# SCH_floatproj_2024-04-08.net
KiCad netlist of a schematic drawn in EasyEDA
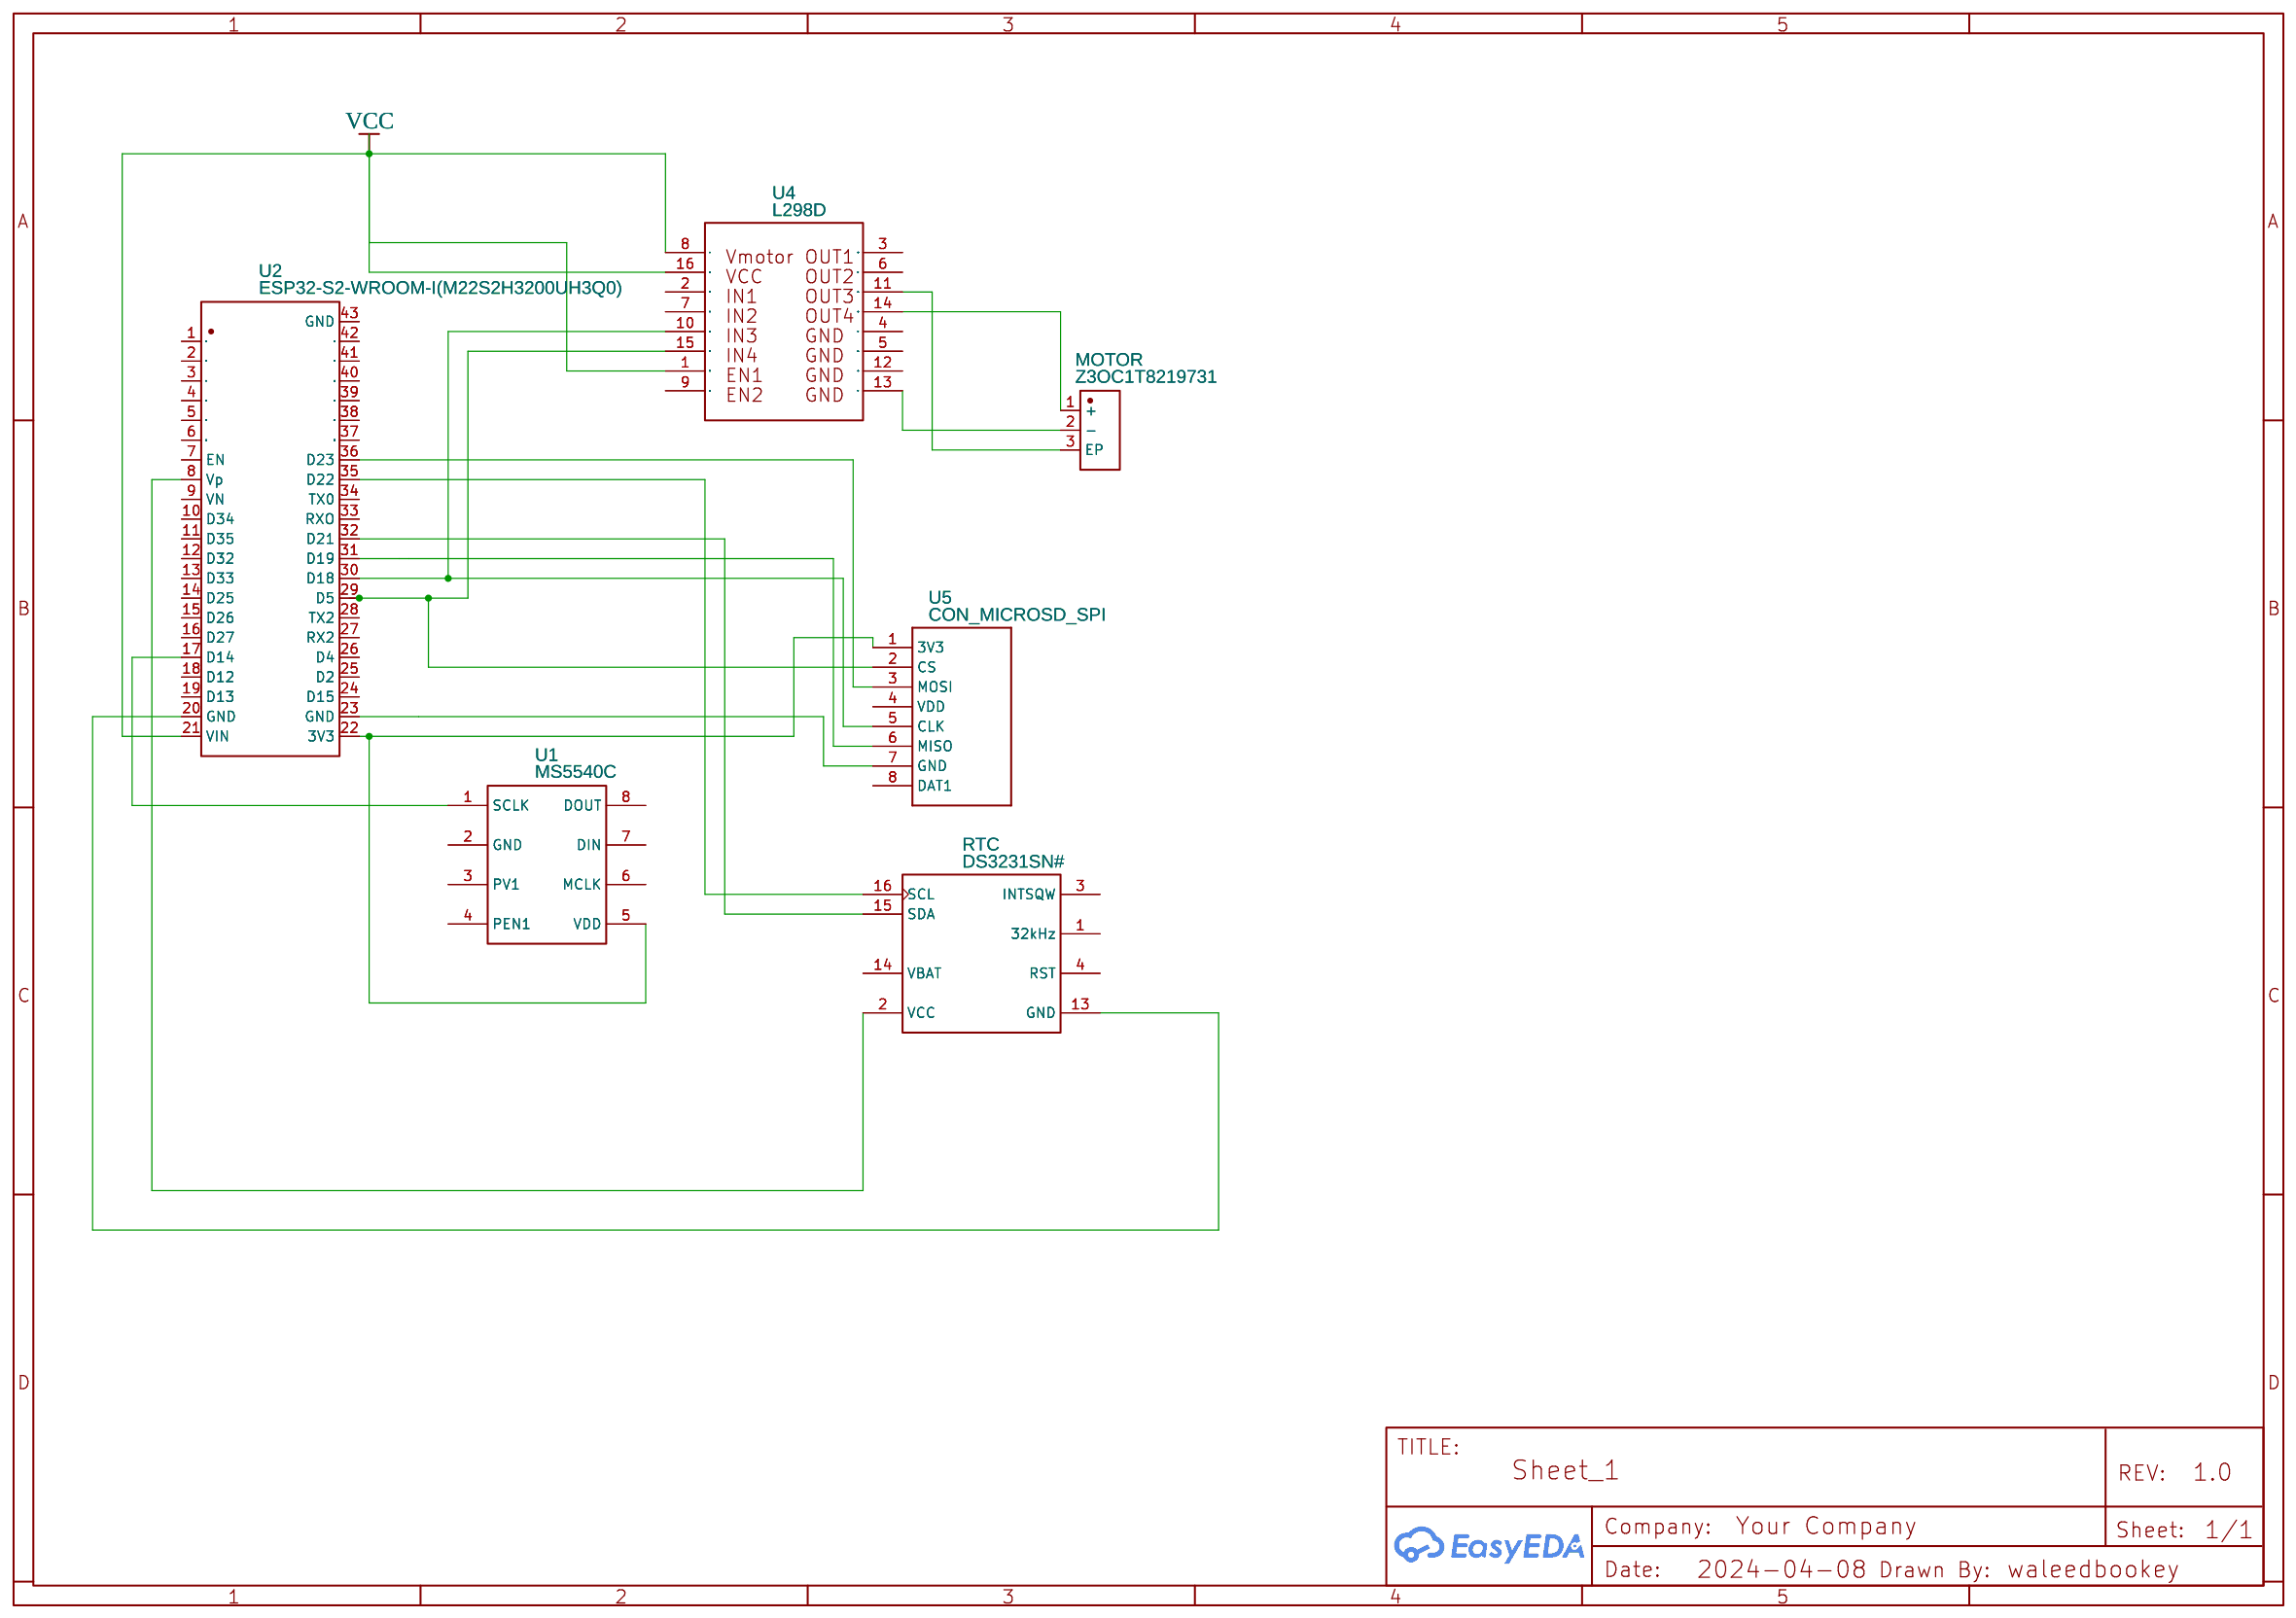
[diagram p0: schematic sheet]

(export (version "E")
  (design (tool "Eeschema 10.0.6"))
  (components
    (comp (ref "MOTOR")
      (value "Z3OC1T8219731")
      (fields (field (name "Manufacturer") "KOTL(金龙机电)"))
      (libsource (lib "") (part "Z3OC1T8219731"))
    )
    (comp (ref "RTC")
      (value "DS3231SN#")
      (fields
        (field (name "Manufacturer Part") "DS3231SN#T&R")
        (field (name "Manufacturer") "ADI(亚德诺)/MAXIM(美信)")
      )
      (libsource (lib "") (part "DS3231SN#"))
    )
    (comp (ref "U1") (value "MS5540C") (libsource (lib "") (part "MS5540C")))
    (comp (ref "U2")
      (value "ESP32-S2-WROOM-I(M22S2H3200UH3Q0)")
      (fields (field (name "Manufacturer") "ESPRESSIF(乐鑫)"))
      (libsource (lib "") (part "ESP32-S2-WROOM-I(M22S2H3200UH3Q0)"))
    )
    (comp (ref "U4") (value "L298D") (libsource (lib "") (part "L298D")))
    (comp (ref "U5") (value "CON_MICROSD_SPI") (libsource (lib "") (part "CON_MICROSD")))
  )
  (nets
    (net (code "1") (name "Net-(MOTOR-+)") (class "Default")
      (node (ref "MOTOR") (pin "1") (pinfunction "+_1") (pintype "unspecified"))
      (node (ref "U4") (pin "14") (pinfunction "15_14") (pintype "unspecified"))
    )
    (net (code "2") (name "Net-(MOTOR--)") (class "Default")
      (node (ref "MOTOR") (pin "2") (pinfunction "-_2") (pintype "unspecified"))
      (node (ref "U4") (pin "13") (pinfunction "11_13") (pintype "unspecified"))
    )
    (net (code "3") (name "Net-(MOTOR-EP)") (class "Default")
      (node (ref "MOTOR") (pin "3") (pinfunction "EP_3") (pintype "unspecified"))
      (node (ref "U4") (pin "11") (pinfunction "16_11") (pintype "unspecified"))
    )
    (net (code "4") (name "Net-(RTC-GND)") (class "Default")
      (node (ref "RTC") (pin "13") (pinfunction "GND_13") (pintype "passive"))
      (node (ref "U2") (pin "20") (pinfunction "GND_20") (pintype "unspecified"))
    )
    (net (code "5") (name "Net-(RTC-SCL)") (class "Default")
      (node (ref "RTC") (pin "16") (pinfunction "SCL_16") (pintype "unspecified"))
      (node (ref "U2") (pin "35") (pinfunction "D22_35") (pintype "unspecified"))
    )
    (net (code "6") (name "Net-(RTC-SDA)") (class "Default")
      (node (ref "RTC") (pin "15") (pinfunction "SDA_15") (pintype "bidirectional"))
      (node (ref "U2") (pin "32") (pinfunction "D21_32") (pintype "unspecified"))
    )
    (net (code "7") (name "Net-(RTC-VCC)") (class "Default")
      (node (ref "RTC") (pin "2") (pinfunction "VCC_2") (pintype "passive"))
      (node (ref "U2") (pin "8") (pinfunction "Vp_8") (pintype "unspecified"))
    )
    (net (code "8") (name "Net-(U1-SCLK)") (class "Default")
      (node (ref "U1") (pin "1") (pinfunction "SCLK_1") (pintype "unspecified"))
      (node (ref "U2") (pin "17") (pinfunction "D14_17") (pintype "unspecified"))
    )
    (net (code "9") (name "Net-(U1-VDD)") (class "Default")
      (node (ref "U1") (pin "5") (pinfunction "VDD_5") (pintype "unspecified"))
      (node (ref "U2") (pin "22") (pinfunction "3V3_22") (pintype "unspecified"))
      (node (ref "U5") (pin "1") (pinfunction "3V3_1") (pintype "unspecified"))
    )
    (net (code "10") (name "Net-(U2-D5)") (class "Default")
      (node (ref "U2") (pin "29") (pinfunction "D5_29") (pintype "unspecified"))
      (node (ref "U4") (pin "15") (pinfunction "22_15") (pintype "unspecified"))
      (node (ref "U5") (pin "2") (pinfunction "CS_2") (pintype "unspecified"))
    )
    (net (code "11") (name "Net-(U2-D18)") (class "Default")
      (node (ref "U2") (pin "30") (pinfunction "D18_30") (pintype "unspecified"))
      (node (ref "U4") (pin "10") (pinfunction "23_10") (pintype "unspecified"))
      (node (ref "U5") (pin "5") (pinfunction "CLK_5") (pintype "unspecified"))
    )
    (net (code "12") (name "Net-(U5-GND)") (class "Default")
      (node (ref "U2") (pin "23") (pinfunction "GND_23") (pintype "unspecified"))
      (node (ref "U5") (pin "7") (pinfunction "GND_7") (pintype "unspecified"))
    )
    (net (code "13") (name "Net-(U5-MISO)") (class "Default")
      (node (ref "U2") (pin "31") (pinfunction "D19_31") (pintype "unspecified"))
      (node (ref "U5") (pin "6") (pinfunction "MISO_6") (pintype "unspecified"))
    )
    (net (code "14") (name "Net-(U5-MOSI)") (class "Default")
      (node (ref "U2") (pin "36") (pinfunction "D23_36") (pintype "unspecified"))
      (node (ref "U5") (pin "3") (pinfunction "MOSI_3") (pintype "unspecified"))
    )
    (net (code "15") (name "VCC") (class "Default")
      (node (ref "U2") (pin "21") (pinfunction "VIN_21") (pintype "unspecified"))
      (node (ref "U4") (pin "1") (pinfunction "21_1") (pintype "unspecified"))
      (node (ref "U4") (pin "16") (pinfunction "2_16") (pintype "unspecified"))
      (node (ref "U4") (pin "8") (pinfunction "1_8") (pintype "unspecified"))
    )
    (net (code "16") (name "unconnected-(RTC-32kHz-Pad1)") (class "Default")
      (node (ref "RTC") (pin "1") (pinfunction "32kHz_1") (pintype "unspecified"))
    )
    (net (code "17") (name "unconnected-(RTC-INTSQW-Pad3)") (class "Default")
      (node (ref "RTC") (pin "3") (pinfunction "INTSQW_3") (pintype "unspecified"))
    )
    (net (code "18") (name "unconnected-(RTC-RST-Pad4)") (class "Default")
      (node (ref "RTC") (pin "4") (pinfunction "RST_4") (pintype "bidirectional"))
    )
    (net (code "19") (name "unconnected-(RTC-VBAT-Pad14)") (class "Default")
      (node (ref "RTC") (pin "14") (pinfunction "VBAT_14") (pintype "passive"))
    )
    (net (code "20") (name "unconnected-(U1-DIN-Pad7)") (class "Default")
      (node (ref "U1") (pin "7") (pinfunction "DIN_7") (pintype "unspecified"))
    )
    (net (code "21") (name "unconnected-(U1-DOUT-Pad8)") (class "Default")
      (node (ref "U1") (pin "8") (pinfunction "DOUT_8") (pintype "unspecified"))
    )
    (net (code "22") (name "unconnected-(U1-GND-Pad2)") (class "Default")
      (node (ref "U1") (pin "2") (pinfunction "GND_2") (pintype "unspecified"))
    )
    (net (code "23") (name "unconnected-(U1-MCLK-Pad6)") (class "Default")
      (node (ref "U1") (pin "6") (pinfunction "MCLK_6") (pintype "unspecified"))
    )
    (net (code "24") (name "unconnected-(U1-PEN1-Pad4)") (class "Default")
      (node (ref "U1") (pin "4") (pinfunction "PEN1_4") (pintype "unspecified"))
    )
    (net (code "25") (name "unconnected-(U1-PV1-Pad3)") (class "Default")
      (node (ref "U1") (pin "3") (pinfunction "PV1_3") (pintype "unspecified"))
    )
    (net (code "26") (name "unconnected-(U2-0-Pad4)") (class "Default")
      (node (ref "U2") (pin "4") (pinfunction "0_4") (pintype "unspecified"))
    )
    (net (code "27") (name "unconnected-(U2-0-Pad5)") (class "Default")
      (node (ref "U2") (pin "5") (pinfunction "0_5") (pintype "unspecified"))
    )
    (net (code "28") (name "unconnected-(U2-D2-Pad25)") (class "Default")
      (node (ref "U2") (pin "25") (pinfunction "D2_25") (pintype "unspecified"))
    )
    (net (code "29") (name "unconnected-(U2-D4-Pad26)") (class "Default")
      (node (ref "U2") (pin "26") (pinfunction "D4_26") (pintype "unspecified"))
    )
    (net (code "30") (name "unconnected-(U2-D12-Pad18)") (class "Default")
      (node (ref "U2") (pin "18") (pinfunction "D12_18") (pintype "unspecified"))
    )
    (net (code "31") (name "unconnected-(U2-D13-Pad19)") (class "Default")
      (node (ref "U2") (pin "19") (pinfunction "D13_19") (pintype "unspecified"))
    )
    (net (code "32") (name "unconnected-(U2-D15-Pad24)") (class "Default")
      (node (ref "U2") (pin "24") (pinfunction "D15_24") (pintype "unspecified"))
    )
    (net (code "33") (name "unconnected-(U2-D19-Pad40)") (class "Default")
      (node (ref "U2") (pin "40") (pinfunction "D19_40") (pintype "unspecified"))
    )
    (net (code "34") (name "unconnected-(U2-D21-Pad39)") (class "Default")
      (node (ref "U2") (pin "39") (pinfunction "D21_39") (pintype "unspecified"))
    )
    (net (code "35") (name "unconnected-(U2-D22-Pad41)") (class "Default")
      (node (ref "U2") (pin "41") (pinfunction "D22_41") (pintype "unspecified"))
    )
    (net (code "36") (name "unconnected-(U2-D23-Pad42)") (class "Default")
      (node (ref "U2") (pin "42") (pinfunction "D23_42") (pintype "unspecified"))
    )
    (net (code "37") (name "unconnected-(U2-D25-Pad14)") (class "Default")
      (node (ref "U2") (pin "14") (pinfunction "D25_14") (pintype "unspecified"))
    )
    (net (code "38") (name "unconnected-(U2-D26-Pad15)") (class "Default")
      (node (ref "U2") (pin "15") (pinfunction "D26_15") (pintype "unspecified"))
    )
    (net (code "39") (name "unconnected-(U2-D27-Pad16)") (class "Default")
      (node (ref "U2") (pin "16") (pinfunction "D27_16") (pintype "unspecified"))
    )
    (net (code "40") (name "unconnected-(U2-D32-Pad12)") (class "Default")
      (node (ref "U2") (pin "12") (pinfunction "D32_12") (pintype "unspecified"))
    )
    (net (code "41") (name "unconnected-(U2-D33-Pad13)") (class "Default")
      (node (ref "U2") (pin "13") (pinfunction "D33_13") (pintype "unspecified"))
    )
    (net (code "42") (name "unconnected-(U2-D34-Pad10)") (class "Default")
      (node (ref "U2") (pin "10") (pinfunction "D34_10") (pintype "unspecified"))
    )
    (net (code "43") (name "unconnected-(U2-D35-Pad11)") (class "Default")
      (node (ref "U2") (pin "11") (pinfunction "D35_11") (pintype "unspecified"))
    )
    (net (code "44") (name "unconnected-(U2-EN-Pad1)") (class "Default")
      (node (ref "U2") (pin "1") (pinfunction "EN_1") (pintype "unspecified"))
    )
    (net (code "45") (name "unconnected-(U2-EN-Pad7)") (class "Default")
      (node (ref "U2") (pin "7") (pinfunction "EN_7") (pintype "unspecified"))
    )
    (net (code "46") (name "unconnected-(U2-GND-Pad43)") (class "Default")
      (node (ref "U2") (pin "43") (pinfunction "GND_43") (pintype "unspecified"))
    )
    (net (code "47") (name "unconnected-(U2-IO3-Pad6)") (class "Default")
      (node (ref "U2") (pin "6") (pinfunction "IO3_6") (pintype "unspecified"))
    )
    (net (code "48") (name "unconnected-(U2-RX2-Pad27)") (class "Default")
      (node (ref "U2") (pin "27") (pinfunction "RX2_27") (pintype "unspecified"))
    )
    (net (code "49") (name "unconnected-(U2-RXD0-Pad38)") (class "Default")
      (node (ref "U2") (pin "38") (pinfunction "RXD0_38") (pintype "unspecified"))
    )
    (net (code "50") (name "unconnected-(U2-RXO-Pad33)") (class "Default")
      (node (ref "U2") (pin "33") (pinfunction "RXO_33") (pintype "unspecified"))
    )
    (net (code "51") (name "unconnected-(U2-TX0-Pad34)") (class "Default")
      (node (ref "U2") (pin "34") (pinfunction "TX0_34") (pintype "unspecified"))
    )
    (net (code "52") (name "unconnected-(U2-TX2-Pad28)") (class "Default")
      (node (ref "U2") (pin "28") (pinfunction "TX2_28") (pintype "unspecified"))
    )
    (net (code "53") (name "unconnected-(U2-TXD0-Pad37)") (class "Default")
      (node (ref "U2") (pin "37") (pinfunction "TXD0_37") (pintype "unspecified"))
    )
    (net (code "54") (name "unconnected-(U2-VN-Pad3)") (class "Default")
      (node (ref "U2") (pin "3") (pinfunction "VN_3") (pintype "unspecified"))
    )
    (net (code "55") (name "unconnected-(U2-VN-Pad9)") (class "Default")
      (node (ref "U2") (pin "9") (pinfunction "VN_9") (pintype "unspecified"))
    )
    (net (code "56") (name "unconnected-(U2-VP-Pad2)") (class "Default")
      (node (ref "U2") (pin "2") (pinfunction "VP_2") (pintype "unspecified"))
    )
    (net (code "57") (name "unconnected-(U4-13-Pad5)") (class "Default")
      (node (ref "U4") (pin "5") (pinfunction "13_5") (pintype "unspecified"))
    )
    (net (code "58") (name "unconnected-(U4-14-Pad4)") (class "Default")
      (node (ref "U4") (pin "4") (pinfunction "14_4") (pintype "unspecified"))
    )
    (net (code "59") (name "unconnected-(U4-17-Pad6)") (class "Default")
      (node (ref "U4") (pin "6") (pinfunction "17_6") (pintype "unspecified"))
    )
    (net (code "60") (name "unconnected-(U4-18-Pad3)") (class "Default")
      (node (ref "U4") (pin "3") (pinfunction "18_3") (pintype "unspecified"))
    )
    (net (code "61") (name "unconnected-(U4-20-Pad9)") (class "Default")
      (node (ref "U4") (pin "9") (pinfunction "20_9") (pintype "unspecified"))
    )
    (net (code "62") (name "unconnected-(U4-24-Pad7)") (class "Default")
      (node (ref "U4") (pin "7") (pinfunction "24_7") (pintype "unspecified"))
    )
    (net (code "63") (name "unconnected-(U4-25-Pad2)") (class "Default")
      (node (ref "U4") (pin "2") (pinfunction "25_2") (pintype "unspecified"))
    )
    (net (code "64") (name "unconnected-(U4-Pad12)") (class "Default")
      (node (ref "U4") (pin "12") (pinfunction "12_12") (pintype "unspecified"))
    )
    (net (code "65") (name "unconnected-(U5-DAT1-Pad8)") (class "Default")
      (node (ref "U5") (pin "8") (pinfunction "DAT1_8") (pintype "unspecified"))
    )
    (net (code "66") (name "unconnected-(U5-VDD-Pad4)") (class "Default")
      (node (ref "U5") (pin "4") (pinfunction "VDD_4") (pintype "unspecified"))
    )
  )
)
